# remap.net
KiCad netlist of a schematic drawn in Altium Designer
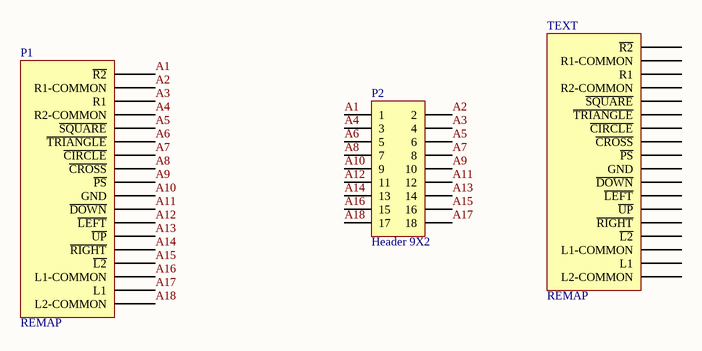
[diagram p0: remap.SchDoc]

(export (version "E")
  (design (tool "Eeschema 10.0.6"))
  (components
    (comp (ref "P1") (value "REMAP") (footprint "remap") (libsource (lib "remap") (part "REMAP")))
    (comp (ref "P2")
      (value "Header 9X2")
      (footprint "HDR2X9")
      (description "Header, 9-Pin, Dual row")
      (fields (field (name "PUBLISHER") "Altium Limited"))
      (libsource (lib "Miscellaneous Connectors") (part "Header 9X2"))
    )
    (comp (ref "TEXT") (value "REMAP") (footprint "text") (libsource (lib "remap") (part "REMAP")))
  )
  (nets
    (net (code "1") (name "/A1") (class "Default")
      (node (ref "P1") (pin "A1") (pinfunction "~{R2}_A1") (pintype "passive"))
      (node (ref "P2") (pin "1") (pinfunction "1_1") (pintype "passive"))
    )
    (net (code "2") (name "/A2") (class "Default")
      (node (ref "P1") (pin "A2") (pinfunction "R1-COMMON_A2") (pintype "passive"))
      (node (ref "P2") (pin "2") (pinfunction "2_2") (pintype "passive"))
    )
    (net (code "3") (name "/A3") (class "Default")
      (node (ref "P1") (pin "A3") (pinfunction "R1_A3") (pintype "passive"))
      (node (ref "P2") (pin "4") (pinfunction "4_4") (pintype "passive"))
    )
    (net (code "4") (name "/A4") (class "Default")
      (node (ref "P1") (pin "A4") (pinfunction "R2-COMMON_A4") (pintype "passive"))
      (node (ref "P2") (pin "3") (pinfunction "3_3") (pintype "passive"))
    )
    (net (code "5") (name "/A5") (class "Default")
      (node (ref "P1") (pin "A5") (pinfunction "~{SQUARE}_A5") (pintype "passive"))
      (node (ref "P2") (pin "6") (pinfunction "6_6") (pintype "passive"))
    )
    (net (code "6") (name "/A6") (class "Default")
      (node (ref "P1") (pin "A6") (pinfunction "~{TRIANGLE}_A6") (pintype "passive"))
      (node (ref "P2") (pin "5") (pinfunction "5_5") (pintype "passive"))
    )
    (net (code "7") (name "/A7") (class "Default")
      (node (ref "P1") (pin "A7") (pinfunction "~{CIRCLE}_A7") (pintype "passive"))
      (node (ref "P2") (pin "8") (pinfunction "8_8") (pintype "passive"))
    )
    (net (code "8") (name "/A8") (class "Default")
      (node (ref "P1") (pin "A8") (pinfunction "~{CROSS}_A8") (pintype "passive"))
      (node (ref "P2") (pin "7") (pinfunction "7_7") (pintype "passive"))
    )
    (net (code "9") (name "/A9") (class "Default")
      (node (ref "P1") (pin "A9") (pinfunction "~{PS}_A9") (pintype "passive"))
      (node (ref "P2") (pin "10") (pinfunction "10_10") (pintype "passive"))
    )
    (net (code "10") (name "/A10") (class "Default")
      (node (ref "P1") (pin "A10") (pinfunction "GND_A10") (pintype "passive"))
      (node (ref "P2") (pin "9") (pinfunction "9_9") (pintype "passive"))
    )
    (net (code "11") (name "/A11") (class "Default")
      (node (ref "P1") (pin "A11") (pinfunction "~{DOWN}_A11") (pintype "passive"))
      (node (ref "P2") (pin "12") (pinfunction "12_12") (pintype "passive"))
    )
    (net (code "12") (name "/A12") (class "Default")
      (node (ref "P1") (pin "A12") (pinfunction "~{LEFT}_A12") (pintype "passive"))
      (node (ref "P2") (pin "11") (pinfunction "11_11") (pintype "passive"))
    )
    (net (code "13") (name "/A13") (class "Default")
      (node (ref "P1") (pin "A13") (pinfunction "~{UP}_A13") (pintype "passive"))
      (node (ref "P2") (pin "14") (pinfunction "14_14") (pintype "passive"))
    )
    (net (code "14") (name "/A14") (class "Default")
      (node (ref "P1") (pin "A14") (pinfunction "~{RIGHT}_A14") (pintype "passive"))
      (node (ref "P2") (pin "13") (pinfunction "13_13") (pintype "passive"))
    )
    (net (code "15") (name "/A15") (class "Default")
      (node (ref "P1") (pin "A15") (pinfunction "~{L2}_A15") (pintype "passive"))
      (node (ref "P2") (pin "16") (pinfunction "16_16") (pintype "passive"))
    )
    (net (code "16") (name "/A16") (class "Default")
      (node (ref "P1") (pin "A16") (pinfunction "L1-COMMON_A16") (pintype "passive"))
      (node (ref "P2") (pin "15") (pinfunction "15_15") (pintype "passive"))
    )
    (net (code "17") (name "/A17") (class "Default")
      (node (ref "P1") (pin "A17") (pinfunction "L1_A17") (pintype "passive"))
      (node (ref "P2") (pin "18") (pinfunction "18_18") (pintype "passive"))
    )
    (net (code "18") (name "/A18") (class "Default")
      (node (ref "P1") (pin "A18") (pinfunction "L2-COMMON_A18") (pintype "passive"))
      (node (ref "P2") (pin "17") (pinfunction "17_17") (pintype "passive"))
    )
    (net (code "19") (name "unconnected-(TEXT-GND-PadA10)") (class "Default")
      (node (ref "TEXT") (pin "A10") (pinfunction "GND_A10") (pintype "passive"))
    )
    (net (code "20") (name "unconnected-(TEXT-L1-COMMON-PadA16)") (class "Default")
      (node (ref "TEXT") (pin "A16") (pinfunction "L1-COMMON_A16") (pintype "passive"))
    )
    (net (code "21") (name "unconnected-(TEXT-L1-PadA17)") (class "Default")
      (node (ref "TEXT") (pin "A17") (pinfunction "L1_A17") (pintype "passive"))
    )
    (net (code "22") (name "unconnected-(TEXT-L2-COMMON-PadA18)") (class "Default")
      (node (ref "TEXT") (pin "A18") (pinfunction "L2-COMMON_A18") (pintype "passive"))
    )
    (net (code "23") (name "unconnected-(TEXT-R1-COMMON-PadA2)") (class "Default")
      (node (ref "TEXT") (pin "A2") (pinfunction "R1-COMMON_A2") (pintype "passive"))
    )
    (net (code "24") (name "unconnected-(TEXT-R1-PadA3)") (class "Default")
      (node (ref "TEXT") (pin "A3") (pinfunction "R1_A3") (pintype "passive"))
    )
    (net (code "25") (name "unconnected-(TEXT-R2-COMMON-PadA4)") (class "Default")
      (node (ref "TEXT") (pin "A4") (pinfunction "R2-COMMON_A4") (pintype "passive"))
    )
    (net (code "26") (name "unconnected-(TEXT-~{CIRCLE}-PadA7)") (class "Default")
      (node (ref "TEXT") (pin "A7") (pinfunction "~{CIRCLE}_A7") (pintype "passive"))
    )
    (net (code "27") (name "unconnected-(TEXT-~{CROSS}-PadA8)") (class "Default")
      (node (ref "TEXT") (pin "A8") (pinfunction "~{CROSS}_A8") (pintype "passive"))
    )
    (net (code "28") (name "unconnected-(TEXT-~{DOWN}-PadA11)") (class "Default")
      (node (ref "TEXT") (pin "A11") (pinfunction "~{DOWN}_A11") (pintype "passive"))
    )
    (net (code "29") (name "unconnected-(TEXT-~{L2}-PadA15)") (class "Default")
      (node (ref "TEXT") (pin "A15") (pinfunction "~{L2}_A15") (pintype "passive"))
    )
    (net (code "30") (name "unconnected-(TEXT-~{LEFT}-PadA12)") (class "Default")
      (node (ref "TEXT") (pin "A12") (pinfunction "~{LEFT}_A12") (pintype "passive"))
    )
    (net (code "31") (name "unconnected-(TEXT-~{PS}-PadA9)") (class "Default")
      (node (ref "TEXT") (pin "A9") (pinfunction "~{PS}_A9") (pintype "passive"))
    )
    (net (code "32") (name "unconnected-(TEXT-~{R2}-PadA1)") (class "Default")
      (node (ref "TEXT") (pin "A1") (pinfunction "~{R2}_A1") (pintype "passive"))
    )
    (net (code "33") (name "unconnected-(TEXT-~{RIGHT}-PadA14)") (class "Default")
      (node (ref "TEXT") (pin "A14") (pinfunction "~{RIGHT}_A14") (pintype "passive"))
    )
    (net (code "34") (name "unconnected-(TEXT-~{SQUARE}-PadA5)") (class "Default")
      (node (ref "TEXT") (pin "A5") (pinfunction "~{SQUARE}_A5") (pintype "passive"))
    )
    (net (code "35") (name "unconnected-(TEXT-~{TRIANGLE}-PadA6)") (class "Default")
      (node (ref "TEXT") (pin "A6") (pinfunction "~{TRIANGLE}_A6") (pintype "passive"))
    )
    (net (code "36") (name "unconnected-(TEXT-~{UP}-PadA13)") (class "Default")
      (node (ref "TEXT") (pin "A13") (pinfunction "~{UP}_A13") (pintype "passive"))
    )
  )
)
